# maul3.net
KiCad netlist of a schematic drawn in EAGLE
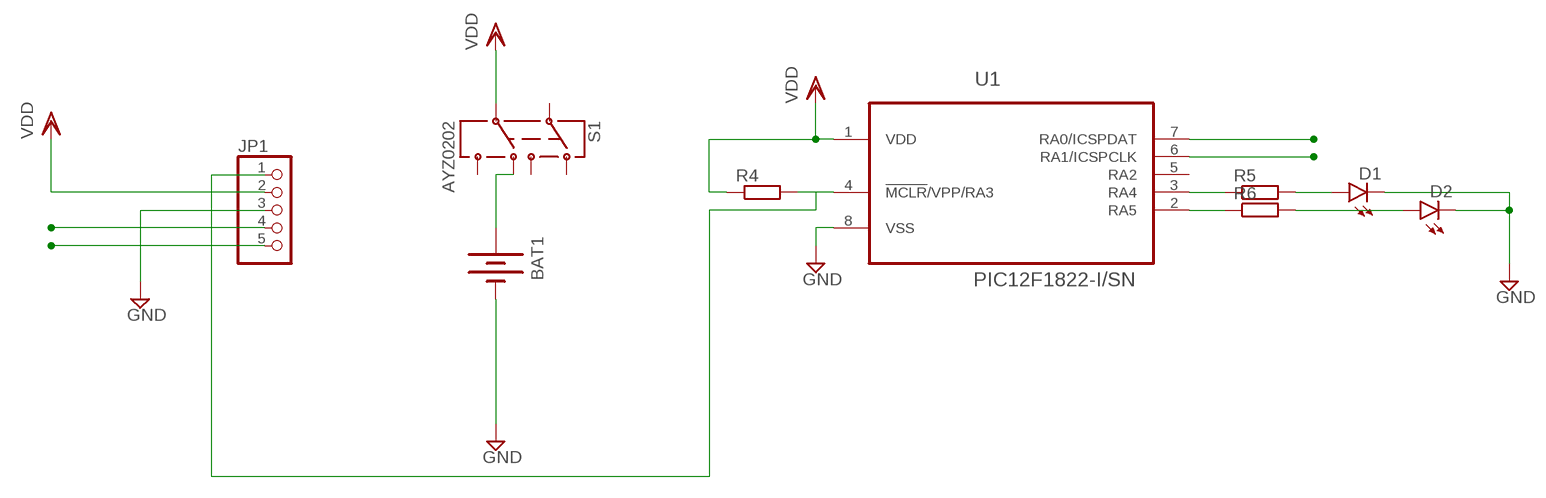
[diagram p0: schematic, sheet 1]

(export (version "E")
  (design (tool "Eeschema 10.0.6"))
  (components
    (comp (ref "BAT1")
      (value "BATTERYFOB")
      (footprint "eagle-import:BATTERY_20MM_PTH_COMPACT")
      (libsource (lib "eagle-import") (part "BATTERYFOB"))
    )
    (comp (ref "D1")
      (value "LED1206")
      (footprint "eagle-import:LED-1206")
      (libsource (lib "eagle-import") (part "LED1206"))
    )
    (comp (ref "D2")
      (value "LED1206")
      (footprint "eagle-import:LED-1206")
      (libsource (lib "eagle-import") (part "LED1206"))
    )
    (comp (ref "JP1")
      (value "PINHD-1X5")
      (footprint "eagle-import:1X05")
      (libsource (lib "eagle-import") (part "PINHD-1X5"))
    )
    (comp (ref "R4")
      (value "R-EU_R1206")
      (footprint "eagle-import:R1206")
      (libsource (lib "eagle-import") (part "R-EU_R1206"))
    )
    (comp (ref "R5")
      (value "R-EU_R1206")
      (footprint "eagle-import:R1206")
      (libsource (lib "eagle-import") (part "R-EU_R1206"))
    )
    (comp (ref "R6")
      (value "R-EU_R1206")
      (footprint "eagle-import:R1206")
      (libsource (lib "eagle-import") (part "R-EU_R1206"))
    )
    (comp (ref "S1")
      (value "AYZ0202")
      (footprint "eagle-import:AYZ0202")
      (libsource (lib "eagle-import") (part "AYZ0202"))
    )
    (comp (ref "U1")
      (value "PIC12F1822-I/SN")
      (footprint "eagle-import:SOIC127P600X175-8N")
      (libsource (lib "eagle-import") (part "PIC12F1822-I/SN"))
    )
  )
  (nets
    (net (code "1") (name "/ICSPCLK") (class "Default")
      (node (ref "JP1") (pin "5") (pinfunction "5_5") (pintype "passive"))
      (node (ref "U1") (pin "6") (pinfunction "RA1/ICSPCLK_6") (pintype "bidirectional"))
    )
    (net (code "2") (name "/ICSPDAT") (class "Default")
      (node (ref "JP1") (pin "4") (pinfunction "4_4") (pintype "passive"))
      (node (ref "U1") (pin "7") (pinfunction "RA0/ICSPDAT_7") (pintype "bidirectional"))
    )
    (net (code "3") (name "GND") (class "Default")
      (node (ref "BAT1") (pin "2") (pinfunction "-_2") (pintype "power_in"))
      (node (ref "D1") (pin "C") (pinfunction "C_C") (pintype "passive"))
      (node (ref "D2") (pin "C") (pinfunction "C_C") (pintype "passive"))
      (node (ref "JP1") (pin "3") (pinfunction "3_3") (pintype "passive"))
      (node (ref "U1") (pin "8") (pinfunction "VSS_8") (pintype "power_in"))
    )
    (net (code "4") (name "Net-(BAT1-+)") (class "Default")
      (node (ref "BAT1") (pin "1") (pinfunction "+_1") (pintype "power_in"))
      (node (ref "S1") (pin "6") (pinfunction "4_6") (pintype "bidirectional"))
    )
    (net (code "5") (name "Net-(D1-PadA)") (class "Default")
      (node (ref "D1") (pin "A") (pinfunction "A_A") (pintype "passive"))
      (node (ref "R5") (pin "2") (pinfunction "2_2") (pintype "passive"))
    )
    (net (code "6") (name "Net-(D2-PadA)") (class "Default")
      (node (ref "D2") (pin "A") (pinfunction "A_A") (pintype "passive"))
      (node (ref "R6") (pin "2") (pinfunction "2_2") (pintype "passive"))
    )
    (net (code "7") (name "Net-(U1-RA4)") (class "Default")
      (node (ref "R5") (pin "1") (pinfunction "1_1") (pintype "passive"))
      (node (ref "U1") (pin "3") (pinfunction "RA4_3") (pintype "bidirectional"))
    )
    (net (code "8") (name "Net-(U1-RA5)") (class "Default")
      (node (ref "R6") (pin "1") (pinfunction "1_1") (pintype "passive"))
      (node (ref "U1") (pin "2") (pinfunction "RA5_2") (pintype "bidirectional"))
    )
    (net (code "9") (name "Net-(U1-~{MCLR}{slash}VPP{slash}RA3)") (class "Default")
      (node (ref "JP1") (pin "1") (pinfunction "1_1") (pintype "passive"))
      (node (ref "R4") (pin "2") (pinfunction "2_2") (pintype "passive"))
      (node (ref "U1") (pin "4") (pinfunction "~{MCLR}/VPP/RA3_4") (pintype "input"))
    )
    (net (code "10") (name "VDD") (class "Default")
      (node (ref "JP1") (pin "2") (pinfunction "2_2") (pintype "passive"))
      (node (ref "R4") (pin "1") (pinfunction "1_1") (pintype "passive"))
      (node (ref "S1") (pin "5") (pinfunction "5_5") (pintype "bidirectional"))
      (node (ref "U1") (pin "1") (pinfunction "VDD_1") (pintype "power_in"))
    )
    (net (code "11") (name "unconnected-(S1-1-Pad3)") (class "Default")
      (node (ref "S1") (pin "3") (pinfunction "1_3") (pintype "bidirectional"))
    )
    (net (code "12") (name "unconnected-(S1-3-Pad1)") (class "Default")
      (node (ref "S1") (pin "1") (pinfunction "3_1") (pintype "bidirectional"))
    )
    (net (code "13") (name "unconnected-(S1-6-Pad4)") (class "Default")
      (node (ref "S1") (pin "4") (pinfunction "6_4") (pintype "bidirectional"))
    )
    (net (code "14") (name "unconnected-(S1-Pad2)") (class "Default")
      (node (ref "S1") (pin "2") (pinfunction "2_2") (pintype "bidirectional"))
    )
    (net (code "15") (name "unconnected-(U1-RA2-Pad5)") (class "Default")
      (node (ref "U1") (pin "5") (pinfunction "RA2_5") (pintype "bidirectional"))
    )
  )
)
